# PROIECT_v30.net
KiCad netlist of a schematic drawn in EAGLE
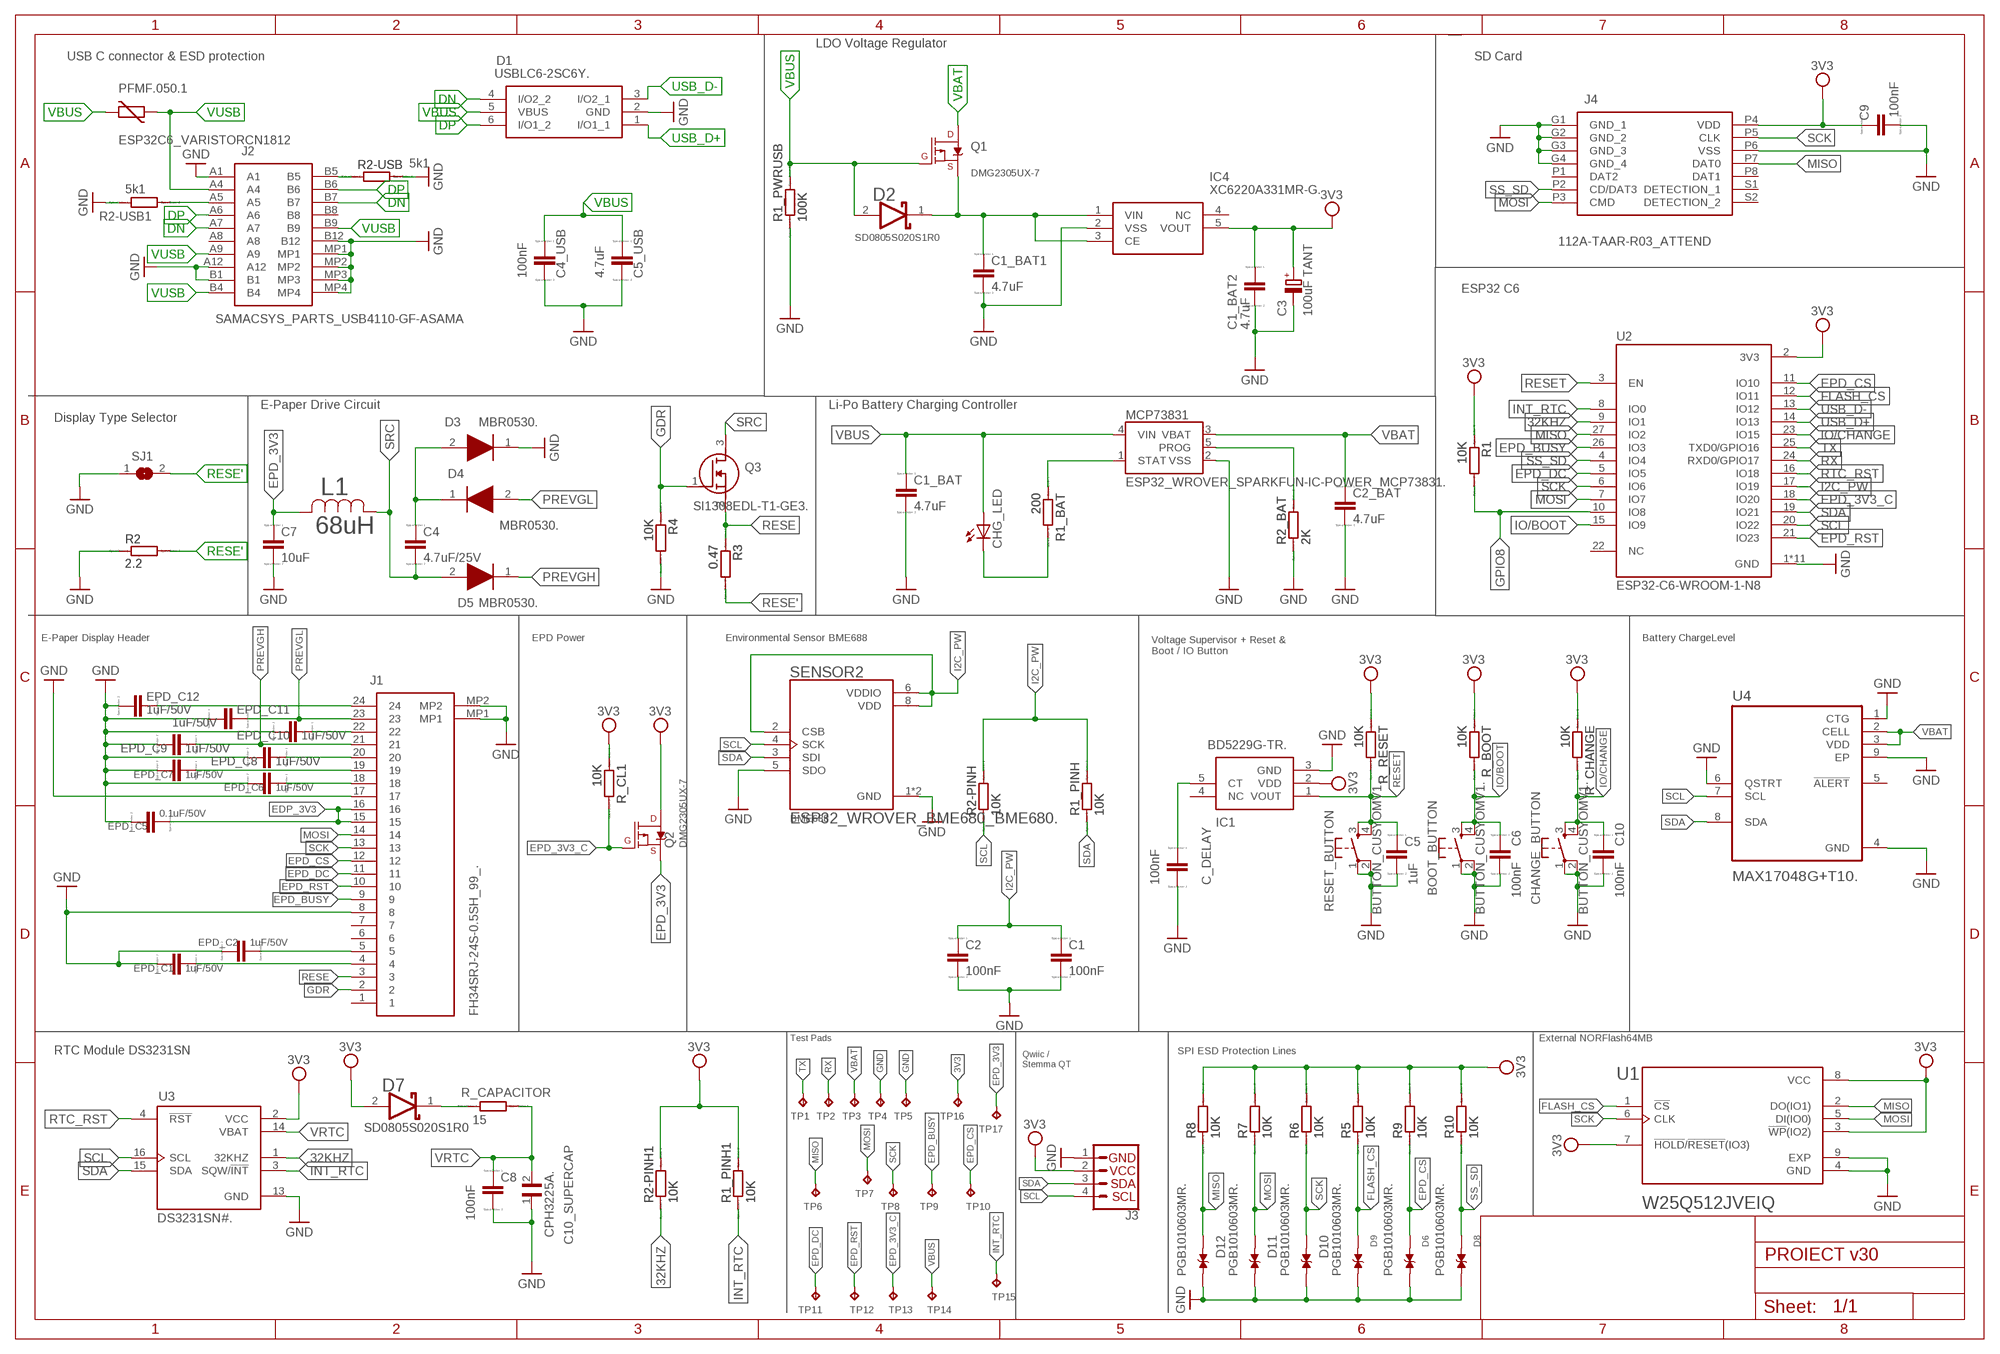
[diagram p0: schematic, sheet 1]

(export (version "E")
  (design (tool "Eeschema 10.0.6"))
  (components
    (comp (ref "BOOT_BUTTON")
      (value "BUTTON_CUSYOMV1.")
      (footprint "eagle-import:MYBUTTON")
      (libsource (lib "eagle-import") (part "BUTTON_CUSYOMV1."))
    )
    (comp (ref "C1")
      (value "100nF")
      (footprint "eagle-import:EAGLE-LTSPICE_C0402")
      (libsource (lib "eagle-import") (part "EAGLE-LTSPICE_CC0402"))
    )
    (comp (ref "C1_BAT")
      (value "4.7uF")
      (footprint "eagle-import:EAGLE-LTSPICE_C0402")
      (libsource (lib "eagle-import") (part "EAGLE-LTSPICE_CC0402"))
    )
    (comp (ref "C1_BAT1")
      (value "4.7uF")
      (footprint "eagle-import:EAGLE-LTSPICE_C0402")
      (libsource (lib "eagle-import") (part "EAGLE-LTSPICE_CC0402"))
    )
    (comp (ref "C1_BAT2")
      (value "4.7uF")
      (footprint "eagle-import:EAGLE-LTSPICE_C0402")
      (libsource (lib "eagle-import") (part "EAGLE-LTSPICE_CC0402"))
    )
    (comp (ref "C2")
      (value "100nF")
      (footprint "eagle-import:EAGLE-LTSPICE_C0402")
      (libsource (lib "eagle-import") (part "EAGLE-LTSPICE_CC0402"))
    )
    (comp (ref "C2_BAT")
      (value "4.7uF")
      (footprint "eagle-import:EAGLE-LTSPICE_C0402")
      (libsource (lib "eagle-import") (part "EAGLE-LTSPICE_CC0402"))
    )
    (comp (ref "C3")
      (value "100uF TANT")
      (footprint "eagle-import:RCL_CT3528")
      (libsource (lib "eagle-import") (part "RCL_CPOL-EUCT3528"))
    )
    (comp (ref "C4")
      (value "4.7uF/25V")
      (footprint "eagle-import:EAGLE-LTSPICE_C0402")
      (libsource (lib "eagle-import") (part "EAGLE-LTSPICE_CC0402"))
    )
    (comp (ref "C4_USB")
      (value "100nF")
      (footprint "eagle-import:EAGLE-LTSPICE_C0402")
      (libsource (lib "eagle-import") (part "EAGLE-LTSPICE_CC0402"))
    )
    (comp (ref "C5")
      (value "1uF")
      (footprint "eagle-import:EAGLE-LTSPICE_C0402")
      (libsource (lib "eagle-import") (part "EAGLE-LTSPICE_CC0402"))
    )
    (comp (ref "C5_USB")
      (value "4.7uF")
      (footprint "eagle-import:EAGLE-LTSPICE_C0402")
      (libsource (lib "eagle-import") (part "EAGLE-LTSPICE_CC0402"))
    )
    (comp (ref "C6")
      (value "100nF")
      (footprint "eagle-import:EAGLE-LTSPICE_C0402")
      (libsource (lib "eagle-import") (part "EAGLE-LTSPICE_CC0402"))
    )
    (comp (ref "C7")
      (value "10uF")
      (footprint "eagle-import:EAGLE-LTSPICE_C0402")
      (libsource (lib "eagle-import") (part "EAGLE-LTSPICE_CC0402"))
    )
    (comp (ref "C8")
      (value "100nF")
      (footprint "eagle-import:EAGLE-LTSPICE_C0402")
      (libsource (lib "eagle-import") (part "EAGLE-LTSPICE_CC0402"))
    )
    (comp (ref "C9")
      (value "100nF")
      (footprint "eagle-import:EAGLE-LTSPICE_C0402")
      (libsource (lib "eagle-import") (part "EAGLE-LTSPICE_CC0402"))
    )
    (comp (ref "C10")
      (value "100nF")
      (footprint "eagle-import:EAGLE-LTSPICE_C0402")
      (libsource (lib "eagle-import") (part "EAGLE-LTSPICE_CC0402"))
    )
    (comp (ref "C10_SUPERCAP")
      (value "CPH3225A.")
      (footprint "eagle-import:CAPCP3225X100N")
      (libsource (lib "eagle-import") (part "CPH3225A."))
    )
    (comp (ref "CHANGE_BUTTON")
      (value "BUTTON_CUSYOMV1.")
      (footprint "eagle-import:MYBUTTON")
      (libsource (lib "eagle-import") (part "BUTTON_CUSYOMV1."))
    )
    (comp (ref "CHG_LED")
      (value "ADAFRUIT_LEDCHIP-LED0603")
      (footprint "eagle-import:ADAFRUIT_CHIP-LED0603")
      (libsource (lib "eagle-import") (part "ADAFRUIT_LEDCHIP-LED0603"))
    )
    (comp (ref "C_DELAY")
      (value "100nF")
      (footprint "eagle-import:EAGLE-LTSPICE_C0402")
      (libsource (lib "eagle-import") (part "EAGLE-LTSPICE_CC0402"))
    )
    (comp (ref "D1")
      (value "USBLC6-2SC6Y.")
      (footprint "eagle-import:SOT95P280X145-6N")
      (libsource (lib "eagle-import") (part "USBLC6-2SC6Y."))
    )
    (comp (ref "D2")
      (value "ESP32_WROVER_AVX---SD0805S020S1R0_AVX_SD0805S020S1R0_0_0AVX_SD0805S020S1R0_0_0")
      (footprint "eagle-import:ESP32_WROVER_AVX---SD0805S020S1R0_AVX_SD0805S020S1R0_0")
      (fields (field (name "NUME") "SD0805S020S1R0"))
      (libsource (lib "eagle-import") (part "ESP32_WROVER_AVX---SD0805S020S1R0_AVX_SD0805S020S1R0_0_0AVX_SD0805S020S1R0_0_0"))
    )
    (comp (ref "D3")
      (value "MBR0530.")
      (footprint "eagle-import:SOD3716X135N")
      (libsource (lib "eagle-import") (part "MBR0530."))
    )
    (comp (ref "D4")
      (value "MBR0530.")
      (footprint "eagle-import:SOD3716X135N")
      (libsource (lib "eagle-import") (part "MBR0530."))
    )
    (comp (ref "D5")
      (value "MBR0530.")
      (footprint "eagle-import:SOD3716X135N")
      (libsource (lib "eagle-import") (part "MBR0530."))
    )
    (comp (ref "D6")
      (value "PGB1010603MR.")
      (footprint "eagle-import:DIOC1608X36N")
      (libsource (lib "eagle-import") (part "PGB1010603MR."))
    )
    (comp (ref "D7")
      (value "ESP32_WROVER_AVX---SD0805S020S1R0_AVX_SD0805S020S1R0_0_0AVX_SD0805S020S1R0_0_0")
      (footprint "eagle-import:ESP32_WROVER_AVX---SD0805S020S1R0_AVX_SD0805S020S1R0_0")
      (fields (field (name "NUME") "SD0805S020S1R0"))
      (libsource (lib "eagle-import") (part "ESP32_WROVER_AVX---SD0805S020S1R0_AVX_SD0805S020S1R0_0_0AVX_SD0805S020S1R0_0_0"))
    )
    (comp (ref "D8")
      (value "PGB1010603MR.")
      (footprint "eagle-import:DIOC1608X36N")
      (libsource (lib "eagle-import") (part "PGB1010603MR."))
    )
    (comp (ref "D9")
      (value "PGB1010603MR.")
      (footprint "eagle-import:DIOC1608X36N")
      (libsource (lib "eagle-import") (part "PGB1010603MR."))
    )
    (comp (ref "D10")
      (value "PGB1010603MR.")
      (footprint "eagle-import:DIOC1608X36N")
      (libsource (lib "eagle-import") (part "PGB1010603MR."))
    )
    (comp (ref "D11")
      (value "PGB1010603MR.")
      (footprint "eagle-import:DIOC1608X36N")
      (libsource (lib "eagle-import") (part "PGB1010603MR."))
    )
    (comp (ref "D12")
      (value "PGB1010603MR.")
      (footprint "eagle-import:DIOC1608X36N")
      (libsource (lib "eagle-import") (part "PGB1010603MR."))
    )
    (comp (ref "EPD_C1")
      (value "1uF/50V")
      (footprint "eagle-import:EAGLE-LTSPICE_C0402")
      (libsource (lib "eagle-import") (part "EAGLE-LTSPICE_CC0402"))
    )
    (comp (ref "EPD_C2")
      (value "1uF/50V")
      (footprint "eagle-import:EAGLE-LTSPICE_C0402")
      (libsource (lib "eagle-import") (part "EAGLE-LTSPICE_CC0402"))
    )
    (comp (ref "EPD_C5")
      (value "0.1uF/50V")
      (footprint "eagle-import:EAGLE-LTSPICE_C0402")
      (libsource (lib "eagle-import") (part "EAGLE-LTSPICE_CC0402"))
    )
    (comp (ref "EPD_C6")
      (value "1uF/50V")
      (footprint "eagle-import:EAGLE-LTSPICE_C0402")
      (libsource (lib "eagle-import") (part "EAGLE-LTSPICE_CC0402"))
    )
    (comp (ref "EPD_C7")
      (value "1uF/50V")
      (footprint "eagle-import:EAGLE-LTSPICE_C0402")
      (libsource (lib "eagle-import") (part "EAGLE-LTSPICE_CC0402"))
    )
    (comp (ref "EPD_C8")
      (value "1uF/50V")
      (footprint "eagle-import:EAGLE-LTSPICE_C0402")
      (libsource (lib "eagle-import") (part "EAGLE-LTSPICE_CC0402"))
    )
    (comp (ref "EPD_C9")
      (value "1uF/50V")
      (footprint "eagle-import:EAGLE-LTSPICE_C0402")
      (libsource (lib "eagle-import") (part "EAGLE-LTSPICE_CC0402"))
    )
    (comp (ref "EPD_C10")
      (value "1uF/50V")
      (footprint "eagle-import:EAGLE-LTSPICE_C0402")
      (libsource (lib "eagle-import") (part "EAGLE-LTSPICE_CC0402"))
    )
    (comp (ref "EPD_C11")
      (value "1uF/50V")
      (footprint "eagle-import:EAGLE-LTSPICE_C0402")
      (libsource (lib "eagle-import") (part "EAGLE-LTSPICE_CC0402"))
    )
    (comp (ref "EPD_C12")
      (value "1uF/50V")
      (footprint "eagle-import:EAGLE-LTSPICE_C0402")
      (libsource (lib "eagle-import") (part "EAGLE-LTSPICE_CC0402"))
    )
    (comp (ref "IC1")
      (value "BD5229G-TR.")
      (footprint "eagle-import:SOT95P280X125-5N")
      (libsource (lib "eagle-import") (part "BD5229G-TR."))
    )
    (comp (ref "IC4")
      (value "XC6220A331MR-G.")
      (footprint "eagle-import:SOT95P280X120-5N")
      (libsource (lib "eagle-import") (part "XC6220A331MR-G."))
    )
    (comp (ref "J1")
      (value "FH34SRJ-24S-0.5SH_99_.")
      (footprint "eagle-import:FH34SRJ24S05SH99")
      (libsource (lib "eagle-import") (part "FH34SRJ-24S-0.5SH_99_."))
    )
    (comp (ref "J2")
      (value "SAMACSYS_PARTS_USB4110-GF-ASAMA")
      (footprint "eagle-import:SAMACSYS_PARTS_USB4110GFA")
      (libsource (lib "eagle-import") (part "SAMACSYS_PARTS_USB4110-GF-ASAMA"))
    )
    (comp (ref "J3")
      (value "QWIIC_RIGHT_ANGLE")
      (footprint "eagle-import:JST04_1MM_RA")
      (libsource (lib "eagle-import") (part "QWIIC_CONNECTORJS-1MM"))
    )
    (comp (ref "J4")
      (value "112A-TAAR-R03_ATTEND")
      (footprint "eagle-import:112ATAARR03ATTEND")
      (fields (field (name "MANUFACTURER_PART_NUMBER") "112A-TAAR-R03 ATTEND"))
      (libsource (lib "eagle-import") (part "112A-TAAR-R03_ATTEND"))
    )
    (comp (ref "L1")
      (value "68uH")
      (footprint "eagle-import:IND_4828-WE-TPC_WRE")
      (libsource (lib "eagle-import") (part "744043680IND_4828-WE-TPC_WRE"))
    )
    (comp (ref "MCP73831")
      (value "ESP32_WROVER_SPARKFUN-IC-POWER_MCP73831.")
      (footprint "eagle-import:ESP32_WROVER_SPARKFUN-IC-POWER_SOT23-5")
      (libsource (lib "eagle-import") (part "ESP32_WROVER_SPARKFUN-IC-POWER_MCP73831."))
    )
    (comp (ref "PFMF.050.1")
      (value "ESP32C6_VARISTORCN1812")
      (footprint "eagle-import:ESP32C6_VARISTOR_CT_CN1812")
      (libsource (lib "eagle-import") (part "ESP32C6_VARISTORCN1812"))
    )
    (comp (ref "Q1")
      (value "20V/4.2A/52mΩ/1.4W")
      (footprint "eagle-import:ESP32_WROVER_SPARKFUN-DISCRETESEMI_SOT23-3")
      (fields (field (name "NUME") "DMG2305UX-7"))
      (libsource (lib "eagle-import") (part "ESP32_WROVER_SPARKFUN-DISCRETESEMI_MOSFET_PCH-DMG2305UX-7"))
    )
    (comp (ref "Q2")
      (value "20V/4.2A/52mΩ/1.4W")
      (footprint "eagle-import:ESP32_WROVER_SPARKFUN-DISCRETESEMI_SOT23-3")
      (fields (field (name "Q2") "DMG2305UX-7"))
      (libsource (lib "eagle-import") (part "ESP32_WROVER_SPARKFUN-DISCRETESEMI_MOSFET_PCH-DMG2305UX-7"))
    )
    (comp (ref "Q3")
      (value "SI1308EDL-T1-GE3.")
      (footprint "eagle-import:SOT65P210X110-3N")
      (libsource (lib "eagle-import") (part "SI1308EDL-T1-GE3."))
    )
    (comp (ref "R1")
      (value "10K")
      (footprint "eagle-import:ESP32_WROVER_EAGLE-LTSPICE_R0402")
      (libsource (lib "eagle-import") (part "ESP32_WROVER_EAGLE-LTSPICE_RR0402"))
    )
    (comp (ref "R1_BAT")
      (value "200")
      (footprint "eagle-import:ESP32_WROVER_EAGLE-LTSPICE_R0402")
      (libsource (lib "eagle-import") (part "ESP32_WROVER_EAGLE-LTSPICE_RR0402"))
    )
    (comp (ref "R1_PINH")
      (value "10K")
      (footprint "eagle-import:ESP32_WROVER_EAGLE-LTSPICE_R0402")
      (libsource (lib "eagle-import") (part "ESP32_WROVER_EAGLE-LTSPICE_RR0402"))
    )
    (comp (ref "R1_PINH1")
      (value "10K")
      (footprint "eagle-import:ESP32_WROVER_EAGLE-LTSPICE_R0402")
      (libsource (lib "eagle-import") (part "ESP32_WROVER_EAGLE-LTSPICE_RR0402"))
    )
    (comp (ref "R1_PWRUSB")
      (value "100K")
      (footprint "eagle-import:ESP32_WROVER_EAGLE-LTSPICE_R0402")
      (libsource (lib "eagle-import") (part "ESP32_WROVER_EAGLE-LTSPICE_RR0402"))
    )
    (comp (ref "R2")
      (value "2.2")
      (footprint "eagle-import:ESP32_WROVER_EAGLE-LTSPICE_R0402")
      (libsource (lib "eagle-import") (part "ESP32_WROVER_EAGLE-LTSPICE_RR0402"))
    )
    (comp (ref "R2-PINH")
      (value "10K")
      (footprint "eagle-import:ESP32_WROVER_EAGLE-LTSPICE_R0402")
      (libsource (lib "eagle-import") (part "ESP32_WROVER_EAGLE-LTSPICE_RR0402"))
    )
    (comp (ref "R2-PINH1")
      (value "10K")
      (footprint "eagle-import:ESP32_WROVER_EAGLE-LTSPICE_R0402")
      (libsource (lib "eagle-import") (part "ESP32_WROVER_EAGLE-LTSPICE_RR0402"))
    )
    (comp (ref "R2-USB")
      (value "5k1")
      (footprint "eagle-import:ESP32_WROVER_EAGLE-LTSPICE_R0402")
      (libsource (lib "eagle-import") (part "ESP32_WROVER_EAGLE-LTSPICE_RR0402"))
    )
    (comp (ref "R2-USB1")
      (value "5k1")
      (footprint "eagle-import:ESP32_WROVER_EAGLE-LTSPICE_R0402")
      (libsource (lib "eagle-import") (part "ESP32_WROVER_EAGLE-LTSPICE_RR0402"))
    )
    (comp (ref "R2_BAT")
      (value "2K")
      (footprint "eagle-import:ESP32_WROVER_EAGLE-LTSPICE_R0402")
      (libsource (lib "eagle-import") (part "ESP32_WROVER_EAGLE-LTSPICE_RR0402"))
    )
    (comp (ref "R3")
      (value "0.47")
      (footprint "eagle-import:ESP32_WROVER_EAGLE-LTSPICE_R0402")
      (libsource (lib "eagle-import") (part "ESP32_WROVER_EAGLE-LTSPICE_RR0402"))
    )
    (comp (ref "R4")
      (value "10K")
      (footprint "eagle-import:ESP32_WROVER_EAGLE-LTSPICE_R0402")
      (libsource (lib "eagle-import") (part "ESP32_WROVER_EAGLE-LTSPICE_RR0402"))
    )
    (comp (ref "R5")
      (value "10K")
      (footprint "eagle-import:ESP32_WROVER_EAGLE-LTSPICE_R0402")
      (libsource (lib "eagle-import") (part "ESP32_WROVER_EAGLE-LTSPICE_RR0402"))
    )
    (comp (ref "R6")
      (value "10K")
      (footprint "eagle-import:ESP32_WROVER_EAGLE-LTSPICE_R0402")
      (libsource (lib "eagle-import") (part "ESP32_WROVER_EAGLE-LTSPICE_RR0402"))
    )
    (comp (ref "R7")
      (value "10K")
      (footprint "eagle-import:ESP32_WROVER_EAGLE-LTSPICE_R0402")
      (libsource (lib "eagle-import") (part "ESP32_WROVER_EAGLE-LTSPICE_RR0402"))
    )
    (comp (ref "R8")
      (value "10K")
      (footprint "eagle-import:ESP32_WROVER_EAGLE-LTSPICE_R0402")
      (libsource (lib "eagle-import") (part "ESP32_WROVER_EAGLE-LTSPICE_RR0402"))
    )
    (comp (ref "R9")
      (value "10K")
      (footprint "eagle-import:ESP32_WROVER_EAGLE-LTSPICE_R0402")
      (libsource (lib "eagle-import") (part "ESP32_WROVER_EAGLE-LTSPICE_RR0402"))
    )
    (comp (ref "R10")
      (value "10K")
      (footprint "eagle-import:ESP32_WROVER_EAGLE-LTSPICE_R0402")
      (libsource (lib "eagle-import") (part "ESP32_WROVER_EAGLE-LTSPICE_RR0402"))
    )
    (comp (ref "RESET_BUTTON")
      (value "BUTTON_CUSYOMV1.")
      (footprint "eagle-import:MYBUTTON")
      (libsource (lib "eagle-import") (part "BUTTON_CUSYOMV1."))
    )
    (comp (ref "R_BOOT")
      (value "10K")
      (footprint "eagle-import:ESP32_WROVER_EAGLE-LTSPICE_R0402")
      (libsource (lib "eagle-import") (part "ESP32_WROVER_EAGLE-LTSPICE_RR0402"))
    )
    (comp (ref "R_CAPACITOR")
      (value "15")
      (footprint "eagle-import:ESP32_WROVER_EAGLE-LTSPICE_R0402")
      (libsource (lib "eagle-import") (part "ESP32_WROVER_EAGLE-LTSPICE_RR0402"))
    )
    (comp (ref "R_CHANGE")
      (value "10K")
      (footprint "eagle-import:ESP32_WROVER_EAGLE-LTSPICE_R0402")
      (libsource (lib "eagle-import") (part "ESP32_WROVER_EAGLE-LTSPICE_RR0402"))
    )
    (comp (ref "R_CL1")
      (value "10K")
      (footprint "eagle-import:ESP32_WROVER_EAGLE-LTSPICE_R0402")
      (libsource (lib "eagle-import") (part "ESP32_WROVER_EAGLE-LTSPICE_RR0402"))
    )
    (comp (ref "R_RESET")
      (value "10K")
      (footprint "eagle-import:ESP32_WROVER_EAGLE-LTSPICE_R0402")
      (libsource (lib "eagle-import") (part "ESP32_WROVER_EAGLE-LTSPICE_RR0402"))
    )
    (comp (ref "SENSOR2")
      (value "ESP32_WROVER_BME680_BME680.")
      (footprint "eagle-import:ESP32_WROVER_BME680_PSON80P300X300X100-8N")
      (fields (field (name "NUME") "BME688"))
      (libsource (lib "eagle-import") (part "ESP32_WROVER_BME680_BME680."))
    )
    (comp (ref "SJ1")
      (value "SJ.")
      (footprint "eagle-import:SJ")
      (libsource (lib "eagle-import") (part "SJ."))
    )
    (comp (ref "TP1")
      (value "TPTP20R")
      (footprint "eagle-import:TP20R")
      (libsource (lib "eagle-import") (part "TPTP20R"))
    )
    (comp (ref "TP2")
      (value "TPTP20R")
      (footprint "eagle-import:TP20R")
      (libsource (lib "eagle-import") (part "TPTP20R"))
    )
    (comp (ref "TP3")
      (value "TPTP20R")
      (footprint "eagle-import:TP20R")
      (libsource (lib "eagle-import") (part "TPTP20R"))
    )
    (comp (ref "TP4")
      (value "TPTP20R")
      (footprint "eagle-import:TP20R")
      (libsource (lib "eagle-import") (part "TPTP20R"))
    )
    (comp (ref "TP5")
      (value "TPTP20R")
      (footprint "eagle-import:TP20R")
      (libsource (lib "eagle-import") (part "TPTP20R"))
    )
    (comp (ref "TP6")
      (value "TPTP20R")
      (footprint "eagle-import:TP20R")
      (libsource (lib "eagle-import") (part "TPTP20R"))
    )
    (comp (ref "TP7")
      (value "TPTP20R")
      (footprint "eagle-import:TP20R")
      (libsource (lib "eagle-import") (part "TPTP20R"))
    )
    (comp (ref "TP8")
      (value "TPTP20R")
      (footprint "eagle-import:TP20R")
      (libsource (lib "eagle-import") (part "TPTP20R"))
    )
    (comp (ref "TP9")
      (value "TPTP20R")
      (footprint "eagle-import:TP20R")
      (libsource (lib "eagle-import") (part "TPTP20R"))
    )
    (comp (ref "TP10")
      (value "TPTP20R")
      (footprint "eagle-import:TP20R")
      (libsource (lib "eagle-import") (part "TPTP20R"))
    )
    (comp (ref "TP11")
      (value "TPTP20R")
      (footprint "eagle-import:TP20R")
      (libsource (lib "eagle-import") (part "TPTP20R"))
    )
    (comp (ref "TP12")
      (value "TPTP20R")
      (footprint "eagle-import:TP20R")
      (libsource (lib "eagle-import") (part "TPTP20R"))
    )
    (comp (ref "TP13")
      (value "TPTP20R")
      (footprint "eagle-import:TP20R")
      (libsource (lib "eagle-import") (part "TPTP20R"))
    )
    (comp (ref "TP14")
      (value "TPTP20R")
      (footprint "eagle-import:TP20R")
      (libsource (lib "eagle-import") (part "TPTP20R"))
    )
    (comp (ref "TP15")
      (value "TPTP20R")
      (footprint "eagle-import:TP20R")
      (libsource (lib "eagle-import") (part "TPTP20R"))
    )
    (comp (ref "TP16")
      (value "TPTP20R")
      (footprint "eagle-import:TP20R")
      (libsource (lib "eagle-import") (part "TPTP20R"))
    )
    (comp (ref "TP17")
      (value "TPTP20R")
      (footprint "eagle-import:TP20R")
      (libsource (lib "eagle-import") (part "TPTP20R"))
    )
    (comp (ref "U1")
      (value "W25Q512JVEIQ")
      (footprint "eagle-import:SON127P600X800X80-9N")
      (fields (field (name "MF") "Winbond Electronics"))
      (libsource (lib "eagle-import") (part "W25Q512JVEIQ"))
    )
    (comp (ref "U2")
      (value "ESP32-C6-WROOM-1-N8")
      (footprint "eagle-import:XCVR_ESP32-C6-WROOM-1-N8")
      (fields (field (name "MF") "Espressif Systems"))
      (libsource (lib "eagle-import") (part "ESP32-C6-WROOM-1-N8"))
    )
    (comp (ref "U3")
      (value "DS3231SN#.")
      (footprint "eagle-import:SOIC127P1032X265-16N")
      (libsource (lib "eagle-import") (part "DS3231SN#."))
    )
    (comp (ref "U4")
      (value "MAX17048G+T10.")
      (footprint "eagle-import:SON50P200X200X80-9N")
      (libsource (lib "eagle-import") (part "MAX17048G+T10."))
    )
  )
  (nets
    (net (code "1") (name "3V3") (class "Default")
      (node (ref "C1_BAT2") (pin "1") (pinfunction "1_1") (pintype "passive"))
      (node (ref "C3") (pin "+") (pinfunction "+_+") (pintype "passive"))
      (node (ref "C9") (pin "1") (pinfunction "1_1") (pintype "passive"))
      (node (ref "D7") (pin "2") (pinfunction "ANODE_2") (pintype "bidirectional"))
      (node (ref "IC1") (pin "2") (pinfunction "VDD_2") (pintype "bidirectional"))
      (node (ref "IC4") (pin "5") (pinfunction "VOUT_5") (pintype "bidirectional"))
      (node (ref "J3") (pin "2") (pinfunction "2_2") (pintype "power_in"))
      (node (ref "J4") (pin "P4") (pinfunction "VDD_P4") (pintype "bidirectional"))
      (node (ref "Q2") (pin "3") (pinfunction "D_3") (pintype "bidirectional"))
      (node (ref "R1") (pin "1") (pinfunction "1_1") (pintype "passive"))
      (node (ref "R10") (pin "2") (pinfunction "2_2") (pintype "passive"))
      (node (ref "R1_PINH1") (pin "2") (pinfunction "2_2") (pintype "passive"))
      (node (ref "R2-PINH1") (pin "2") (pinfunction "2_2") (pintype "passive"))
      (node (ref "R5") (pin "2") (pinfunction "2_2") (pintype "passive"))
      (node (ref "R6") (pin "2") (pinfunction "2_2") (pintype "passive"))
      (node (ref "R7") (pin "2") (pinfunction "2_2") (pintype "passive"))
      (node (ref "R8") (pin "2") (pinfunction "2_2") (pintype "passive"))
      (node (ref "R9") (pin "2") (pinfunction "2_2") (pintype "passive"))
      (node (ref "R_BOOT") (pin "1") (pinfunction "1_1") (pintype "passive"))
      (node (ref "R_CHANGE") (pin "1") (pinfunction "1_1") (pintype "passive"))
      (node (ref "R_CL1") (pin "1") (pinfunction "1_1") (pintype "passive"))
      (node (ref "R_RESET") (pin "1") (pinfunction "1_1") (pintype "passive"))
      (node (ref "TP16") (pin "TP") (pinfunction "TP_TP") (pintype "input"))
      (node (ref "U1") (pin "3") (pinfunction "~{WP}(IO2)_3") (pintype "bidirectional"))
      (node (ref "U1") (pin "7") (pinfunction "~{HOLD}/~{RESET}(IO3)_7") (pintype "bidirectional"))
      (node (ref "U1") (pin "8") (pinfunction "VCC_8") (pintype "power_in"))
      (node (ref "U2") (pin "2") (pinfunction "3V3_2") (pintype "power_in"))
      (node (ref "U3") (pin "2") (pinfunction "VCC_2") (pintype "power_in"))
    )
    (net (code "2") (name "32KHZ") (class "Default")
      (node (ref "R2-PINH1") (pin "1") (pinfunction "1_1") (pintype "passive"))
      (node (ref "U2") (pin "9") (pinfunction "IO1_9") (pintype "bidirectional"))
      (node (ref "U3") (pin "1") (pinfunction "32KHZ_1") (pintype "output"))
    )
    (net (code "3") (name "DN") (class "Default")
      (node (ref "D1") (pin "4") (pinfunction "I/O2_2_4") (pintype "bidirectional"))
      (node (ref "J2") (pin "A7") (pinfunction "A7_A7") (pintype "bidirectional"))
      (node (ref "J2") (pin "B7") (pinfunction "B7_B7") (pintype "bidirectional"))
    )
    (net (code "4") (name "DP") (class "Default")
      (node (ref "D1") (pin "6") (pinfunction "I/O1_2_6") (pintype "bidirectional"))
      (node (ref "J2") (pin "A6") (pinfunction "A6_A6") (pintype "bidirectional"))
      (node (ref "J2") (pin "B6") (pinfunction "B6_B6") (pintype "bidirectional"))
    )
    (net (code "5") (name "EDP_3V3") (class "Default")
      (node (ref "EPD_C5") (pin "1") (pinfunction "1_1") (pintype "passive"))
      (node (ref "J1") (pin "15") (pinfunction "15_15") (pintype "bidirectional"))
      (node (ref "J1") (pin "16") (pinfunction "16_16") (pintype "bidirectional"))
    )
    (net (code "6") (name "EPD_3V3") (class "Default")
      (node (ref "C7") (pin "1") (pinfunction "1_1") (pintype "passive"))
      (node (ref "L1") (pin "2") (pinfunction "2_2") (pintype "passive"))
      (node (ref "Q2") (pin "2") (pinfunction "S_2") (pintype "bidirectional"))
      (node (ref "TP17") (pin "TP") (pinfunction "TP_TP") (pintype "input"))
    )
    (net (code "7") (name "EPD_3V3_C") (class "Default")
      (node (ref "Q2") (pin "1") (pinfunction "G_1") (pintype "bidirectional"))
      (node (ref "R_CL1") (pin "2") (pinfunction "2_2") (pintype "passive"))
      (node (ref "TP13") (pin "TP") (pinfunction "TP_TP") (pintype "input"))
      (node (ref "U2") (pin "18") (pinfunction "IO20_18") (pintype "bidirectional"))
    )
    (net (code "8") (name "EPD_BUSY") (class "Default")
      (node (ref "J1") (pin "9") (pinfunction "9_9") (pintype "bidirectional"))
      (node (ref "TP9") (pin "TP") (pinfunction "TP_TP") (pintype "input"))
      (node (ref "U2") (pin "26") (pinfunction "IO3_26") (pintype "bidirectional"))
    )
    (net (code "9") (name "EPD_CS") (class "Default")
      (node (ref "D6") (pin "1") (pinfunction "1_1") (pintype "passive"))
      (node (ref "J1") (pin "12") (pinfunction "12_12") (pintype "bidirectional"))
      (node (ref "R9") (pin "1") (pinfunction "1_1") (pintype "passive"))
      (node (ref "TP10") (pin "TP") (pinfunction "TP_TP") (pintype "input"))
      (node (ref "U2") (pin "11") (pinfunction "IO10_11") (pintype "bidirectional"))
    )
    (net (code "10") (name "EPD_DC") (class "Default")
      (node (ref "J1") (pin "11") (pinfunction "11_11") (pintype "bidirectional"))
      (node (ref "TP11") (pin "TP") (pinfunction "TP_TP") (pintype "input"))
      (node (ref "U2") (pin "5") (pinfunction "IO5_5") (pintype "bidirectional"))
    )
    (net (code "11") (name "EPD_RST") (class "Default")
      (node (ref "J1") (pin "10") (pinfunction "10_10") (pintype "bidirectional"))
      (node (ref "TP12") (pin "TP") (pinfunction "TP_TP") (pintype "input"))
      (node (ref "U2") (pin "21") (pinfunction "IO23_21") (pintype "bidirectional"))
    )
    (net (code "12") (name "FLASH_CS") (class "Default")
      (node (ref "D9") (pin "1") (pinfunction "1_1") (pintype "passive"))
      (node (ref "R5") (pin "1") (pinfunction "1_1") (pintype "passive"))
      (node (ref "U1") (pin "1") (pinfunction "~{CS}_1") (pintype "input"))
      (node (ref "U2") (pin "12") (pinfunction "IO11_12") (pintype "bidirectional"))
    )
    (net (code "13") (name "GDR") (class "Default")
      (node (ref "J1") (pin "2") (pinfunction "2_2") (pintype "bidirectional"))
      (node (ref "Q3") (pin "1") (pinfunction "G_1") (pintype "bidirectional"))
      (node (ref "R4") (pin "1") (pinfunction "1_1") (pintype "passive"))
    )
    (net (code "14") (name "GND") (class "Default")
      (node (ref "BOOT_BUTTON") (pin "1") (pinfunction "1_1") (pintype "passive"))
      (node (ref "BOOT_BUTTON") (pin "2") (pinfunction "2_2") (pintype "passive"))
      (node (ref "C1") (pin "2") (pinfunction "2_2") (pintype "passive"))
      (node (ref "C10") (pin "2") (pinfunction "2_2") (pintype "passive"))
      (node (ref "C10_SUPERCAP") (pin "1") (pinfunction "1_1") (pintype "passive"))
      (node (ref "C1_BAT") (pin "2") (pinfunction "2_2") (pintype "passive"))
      (node (ref "C1_BAT1") (pin "2") (pinfunction "2_2") (pintype "passive"))
      (node (ref "C1_BAT2") (pin "2") (pinfunction "2_2") (pintype "passive"))
      (node (ref "C2") (pin "2") (pinfunction "2_2") (pintype "passive"))
      (node (ref "C2_BAT") (pin "2") (pinfunction "2_2") (pintype "passive"))
      (node (ref "C3") (pin "-") (pinfunction "-_-") (pintype "passive"))
      (node (ref "C4_USB") (pin "2") (pinfunction "2_2") (pintype "passive"))
      (node (ref "C5") (pin "2") (pinfunction "2_2") (pintype "passive"))
      (node (ref "C5_USB") (pin "2") (pinfunction "2_2") (pintype "passive"))
      (node (ref "C6") (pin "2") (pinfunction "2_2") (pintype "passive"))
      (node (ref "C7") (pin "2") (pinfunction "2_2") (pintype "passive"))
      (node (ref "C8") (pin "2") (pinfunction "2_2") (pintype "passive"))
      (node (ref "C9") (pin "2") (pinfunction "2_2") (pintype "passive"))
      (node (ref "CHANGE_BUTTON") (pin "1") (pinfunction "1_1") (pintype "passive"))
      (node (ref "CHANGE_BUTTON") (pin "2") (pinfunction "2_2") (pintype "passive"))
      (node (ref "C_DELAY") (pin "2") (pinfunction "2_2") (pintype "passive"))
      (node (ref "D1") (pin "2") (pinfunction "GND_2") (pintype "bidirectional"))
      (node (ref "D10") (pin "2") (pinfunction "2_2") (pintype "passive"))
      (node (ref "D11") (pin "2") (pinfunction "2_2") (pintype "passive"))
      (node (ref "D12") (pin "2") (pinfunction "2_2") (pintype "passive"))
      (node (ref "D3") (pin "1") (pinfunction "K_1") (pintype "bidirectional"))
      (node (ref "D6") (pin "2") (pinfunction "2_2") (pintype "passive"))
      (node (ref "D8") (pin "2") (pinfunction "2_2") (pintype "passive"))
      (node (ref "D9") (pin "2") (pinfunction "2_2") (pintype "passive"))
      (node (ref "EPD_C1") (pin "2") (pinfunction "2_2") (pintype "passive"))
      (node (ref "EPD_C10") (pin "2") (pinfunction "2_2") (pintype "passive"))
      (node (ref "EPD_C11") (pin "2") (pinfunction "2_2") (pintype "passive"))
      (node (ref "EPD_C12") (pin "2") (pinfunction "2_2") (pintype "passive"))
      (node (ref "EPD_C2") (pin "2") (pinfunction "2_2") (pintype "passive"))
      (node (ref "EPD_C5") (pin "2") (pinfunction "2_2") (pintype "passive"))
      (node (ref "EPD_C6") (pin "2") (pinfunction "2_2") (pintype "passive"))
      (node (ref "EPD_C7") (pin "2") (pinfunction "2_2") (pintype "passive"))
      (node (ref "EPD_C8") (pin "2") (pinfunction "2_2") (pintype "passive"))
      (node (ref "EPD_C9") (pin "2") (pinfunction "2_2") (pintype "passive"))
      (node (ref "IC1") (pin "3") (pinfunction "GND_3") (pintype "bidirectional"))
      (node (ref "IC4") (pin "2") (pinfunction "VSS_2") (pintype "bidirectional"))
      (node (ref "J1") (pin "17") (pinfunction "17_17") (pintype "bidirectional"))
      (node (ref "J1") (pin "8") (pinfunction "8_8") (pintype "bidirectional"))
      (node (ref "J1") (pin "MP1") (pinfunction "MP1_MP1") (pintype "bidirectional"))
      (node (ref "J1") (pin "MP2") (pinfunction "MP2_MP2") (pintype "bidirectional"))
      (node (ref "J2") (pin "A1") (pinfunction "A1_A1") (pintype "bidirectional"))
      (node (ref "J2") (pin "A12") (pinfunction "A12_A12") (pintype "bidirectional"))
      (node (ref "J2") (pin "B1") (pinfunction "B1_B1") (pintype "bidirectional"))
      (node (ref "J2") (pin "B12") (pinfunction "B12_B12") (pintype "bidirectional"))
      (node (ref "J2") (pin "MP1") (pinfunction "MP1_MP1") (pintype "bidirectional"))
      (node (ref "J2") (pin "MP2") (pinfunction "MP2_MP2") (pintype "bidirectional"))
      (node (ref "J2") (pin "MP3") (pinfunction "MP3_MP3") (pintype "bidirectional"))
      (node (ref "J2") (pin "MP4") (pinfunction "MP4_MP4") (pintype "bidirectional"))
      (node (ref "J3") (pin "1") (pinfunction "1_1") (pintype "power_in"))
      (node (ref "J4") (pin "G1") (pinfunction "GND_1_G1") (pintype "bidirectional"))
      (node (ref "J4") (pin "G2") (pinfunction "GND_2_G2") (pintype "bidirectional"))
      (node (ref "J4") (pin "G3") (pinfunction "GND_3_G3") (pintype "bidirectional"))
      (node (ref "J4") (pin "G4") (pinfunction "GND_4_G4") (pintype "bidirectional"))
      (node (ref "J4") (pin "P6") (pinfunction "VSS_P6") (pintype "bidirectional"))
      (node (ref "MCP73831") (pin "2") (pinfunction "VSS_2") (pintype "power_in"))
      (node (ref "R1_PWRUSB") (pin "1") (pinfunction "1_1") (pintype "passive"))
      (node (ref "R2") (pin "1") (pinfunction "1_1") (pintype "passive"))
      (node (ref "R2-USB") (pin "2") (pinfunction "2_2") (pintype "passive"))
      (node (ref "R2-USB1") (pin "1") (pinfunction "1_1") (pintype "passive"))
      (node (ref "R2_BAT") (pin "1") (pinfunction "1_1") (pintype "passive"))
      (node (ref "R4") (pin "2") (pinfunction "2_2") (pintype "passive"))
      (node (ref "RESET_BUTTON") (pin "1") (pinfunction "1_1") (pintype "passive"))
      (node (ref "RESET_BUTTON") (pin "2") (pinfunction "2_2") (pintype "passive"))
      (node (ref "SENSOR2") (pin "1") (pinfunction "GND_1") (pintype "power_in"))
      (node (ref "SENSOR2") (pin "5") (pinfunction "SDO_5") (pintype "bidirectional"))
      (node (ref "SENSOR2") (pin "7") (pinfunction "GND_7") (pintype "power_in"))
      (node (ref "SJ1") (pin "1") (pinfunction "1_1") (pintype "passive"))
      (node (ref "TP4") (pin "TP") (pinfunction "TP_TP") (pintype "input"))
      (node (ref "TP5") (pin "TP") (pinfunction "TP_TP") (pintype "input"))
      (node (ref "U1") (pin "4") (pinfunction "GND_4") (pintype "power_in"))
      (node (ref "U1") (pin "9") (pinfunction "EXP_9") (pintype "passive"))
      (node (ref "U2") (pin "1") (pinfunction "GND_1") (pintype "power_in"))
      (node (ref "U2") (pin "28") (pinfunction "GND_28") (pintype "power_in"))
      (node (ref "U2") (pin "29_1") (pinfunction "GND_29_1") (pintype "power_in"))
      (node (ref "U2") (pin "29_2") (pinfunction "GND_29_2") (pintype "power_in"))
      (node (ref "U2") (pin "29_3") (pinfunction "GND_29_3") (pintype "power_in"))
      (node (ref "U2") (pin "29_4") (pinfunction "GND_29_4") (pintype "power_in"))
      (node (ref "U2") (pin "29_5") (pinfunction "GND_29_5") (pintype "power_in"))
      (node (ref "U2") (pin "29_6") (pinfunction "GND_29_6") (pintype "power_in"))
      (node (ref "U2") (pin "29_7") (pinfunction "GND_29_7") (pintype "power_in"))
      (node (ref "U2") (pin "29_8") (pinfunction "GND_29_8") (pintype "power_in"))
      (node (ref "U2") (pin "29_9") (pinfunction "GND_29_9") (pintype "power_in"))
      (node (ref "U3") (pin "13") (pinfunction "GND_13") (pintype "power_in"))
      (node (ref "U4") (pin "1") (pinfunction "CTG_1") (pintype "power_in"))
      (node (ref "U4") (pin "4") (pinfunction "GND_4") (pintype "power_in"))
      (node (ref "U4") (pin "6") (pinfunction "QSTRT_6") (pintype "input"))
      (node (ref "U4") (pin "9") (pinfunction "EP_9") (pintype "power_in"))
    )
    (net (code "15") (name "GPIO8") (class "Default")
      (node (ref "R1") (pin "2") (pinfunction "2_2") (pintype "passive"))
      (node (ref "U2") (pin "10") (pinfunction "IO8_10") (pintype "bidirectional"))
    )
    (net (code "16") (name "I2C_PW") (class "Default")
      (node (ref "C1") (pin "1") (pinfunction "1_1") (pintype "passive"))
      (node (ref "C2") (pin "1") (pinfunction "1_1") (pintype "passive"))
      (node (ref "R1_PINH") (pin "2") (pinfunction "2_2") (pintype "passive"))
      (node (ref "R2-PINH") (pin "2") (pinfunction "2_2") (pintype "passive"))
      (node (ref "SENSOR2") (pin "2") (pinfunction "CSB_2") (pintype "input"))
      (node (ref "SENSOR2") (pin "6") (pinfunction "VDDIO_6") (pintype "power_in"))
      (node (ref "SENSOR2") (pin "8") (pinfunction "VDD_8") (pintype "power_in"))
      (node (ref "U2") (pin "17") (pinfunction "IO19_17") (pintype "bidirectional"))
    )
    (net (code "17") (name "INT_RTC") (class "Default")
      (node (ref "R1_PINH1") (pin "1") (pinfunction "1_1") (pintype "passive"))
      (node (ref "TP15") (pin "TP") (pinfunction "TP_TP") (pintype "input"))
      (node (ref "U2") (pin "8") (pinfunction "IO0_8") (pintype "bidirectional"))
      (node (ref "U3") (pin "3") (pinfunction "SQW/~{INT}_3") (pintype "output"))
    )
    (net (code "18") (name "IO{slash}BOOT") (class "Default")
      (node (ref "BOOT_BUTTON") (pin "3") (pinfunction "3_3") (pintype "passive"))
      (node (ref "BOOT_BUTTON") (pin "4") (pinfunction "4_4") (pintype "passive"))
      (node (ref "C6") (pin "1") (pinfunction "1_1") (pintype "passive"))
      (node (ref "R_BOOT") (pin "2") (pinfunction "2_2") (pintype "passive"))
      (node (ref "U2") (pin "15") (pinfunction "IO9_15") (pintype "bidirectional"))
    )
    (net (code "19") (name "IO{slash}CHANGE") (class "Default")
      (node (ref "C10") (pin "1") (pinfunction "1_1") (pintype "passive"))
      (node (ref "CHANGE_BUTTON") (pin "3") (pinfunction "3_3") (pintype "passive"))
      (node (ref "CHANGE_BUTTON") (pin "4") (pinfunction "4_4") (pintype "passive"))
      (node (ref "R_CHANGE") (pin "2") (pinfunction "2_2") (pintype "passive"))
      (node (ref "U2") (pin "23") (pinfunction "IO15_23") (pintype "bidirectional"))
    )
    (net (code "20") (name "MISO") (class "Default")
      (node (ref "D12") (pin "1") (pinfunction "1_1") (pintype "passive"))
      (node (ref "J4") (pin "P7") (pinfunction "DAT0_P7") (pintype "bidirectional"))
      (node (ref "R8") (pin "1") (pinfunction "1_1") (pintype "passive"))
      (node (ref "TP6") (pin "TP") (pinfunction "TP_TP") (pintype "input"))
      (node (ref "U1") (pin "2") (pinfunction "DO(IO1)_2") (pintype "bidirectional"))
      (node (ref "U2") (pin "27") (pinfunction "IO2_27") (pintype "bidirectional"))
    )
    (net (code "21") (name "MOSI") (class "Default")
      (node (ref "D11") (pin "1") (pinfunction "1_1") (pintype "passive"))
      (node (ref "J1") (pin "14") (pinfunction "14_14") (pintype "bidirectional"))
      (node (ref "J4") (pin "P3") (pinfunction "CMD_P3") (pintype "bidirectional"))
      (node (ref "R7") (pin "1") (pinfunction "1_1") (pintype "passive"))
      (node (ref "TP7") (pin "TP") (pinfunction "TP_TP") (pintype "input"))
      (node (ref "U1") (pin "5") (pinfunction "DI(IO0)_5") (pintype "bidirectional"))
      (node (ref "U2") (pin "7") (pinfunction "IO7_7") (pintype "bidirectional"))
    )
    (net (code "22") (name "Net-(CHG_LED-PadC)") (class "Default")
      (node (ref "CHG_LED") (pin "C") (pinfunction "C_C") (pintype "passive"))
      (node (ref "R1_BAT") (pin "2") (pinfunction "2_2") (pintype "passive"))
    )
    (net (code "23") (name "Net-(D2-CATHODE)") (class "Default")
      (node (ref "C1_BAT1") (pin "1") (pinfunction "1_1") (pintype "passive"))
      (node (ref "D2") (pin "1") (pinfunction "CATHODE_1") (pintype "bidirectional"))
      (node (ref "IC4") (pin "1") (pinfunction "VIN_1") (pintype "bidirectional"))
      (node (ref "IC4") (pin "3") (pinfunction "CE_3") (pintype "bidirectional"))
      (node (ref "Q1") (pin "2") (pinfunction "S_2") (pintype "bidirectional"))
    )
    (net (code "24") (name "Net-(D3-A)") (class "Default")
      (node (ref "C4") (pin "1") (pinfunction "1_1") (pintype "passive"))
      (node (ref "D3") (pin "2") (pinfunction "A_2") (pintype "bidirectional"))
      (node (ref "D4") (pin "1") (pinfunction "K_1") (pintype "bidirectional"))
    )
    (net (code "25") (name "Net-(D7-CATHODE)") (class "Default")
      (node (ref "D7") (pin "1") (pinfunction "CATHODE_1") (pintype "bidirectional"))
      (node (ref "R_CAPACITOR") (pin "2") (pinfunction "2_2") (pintype "passive"))
    )
    (net (code "26") (name "Net-(EPD_C1-Pad1)") (class "Default")
      (node (ref "EPD_C1") (pin "1") (pinfunction "1_1") (pintype "passive"))
      (node (ref "J1") (pin "4") (pinfunction "4_4") (pintype "bidirectional"))
    )
    (net (code "27") (name "Net-(EPD_C2-Pad1)") (class "Default")
      (node (ref "EPD_C2") (pin "1") (pinfunction "1_1") (pintype "passive"))
      (node (ref "J1") (pin "5") (pinfunction "5_5") (pintype "bidirectional"))
    )
    (net (code "28") (name "Net-(EPD_C6-Pad1)") (class "Default")
      (node (ref "EPD_C6") (pin "1") (pinfunction "1_1") (pintype "passive"))
      (node (ref "J1") (pin "18") (pinfunction "18_18") (pintype "bidirectional"))
    )
    (net (code "29") (name "Net-(EPD_C7-Pad1)") (class "Default")
      (node (ref "EPD_C7") (pin "1") (pinfunction "1_1") (pintype "passive"))
      (node (ref "J1") (pin "19") (pinfunction "19_19") (pintype "bidirectional"))
    )
    (net (code "30") (name "Net-(EPD_C8-Pad1)") (class "Default")
      (node (ref "EPD_C8") (pin "1") (pinfunction "1_1") (pintype "passive"))
      (node (ref "J1") (pin "20") (pinfunction "20_20") (pintype "bidirectional"))
    )
    (net (code "31") (name "Net-(EPD_C10-Pad1)") (class "Default")
      (node (ref "EPD_C10") (pin "1") (pinfunction "1_1") (pintype "passive"))
      (node (ref "J1") (pin "22") (pinfunction "22_22") (pintype "bidirectional"))
    )
    (net (code "32") (name "Net-(EPD_C12-Pad1)") (class "Default")
      (node (ref "EPD_C12") (pin "1") (pinfunction "1_1") (pintype "passive"))
      (node (ref "J1") (pin "24") (pinfunction "24_24") (pintype "bidirectional"))
    )
    (net (code "33") (name "Net-(IC1-CT)") (class "Default")
      (node (ref "C_DELAY") (pin "1") (pinfunction "1_1") (pintype "passive"))
      (node (ref "IC1") (pin "5") (pinfunction "CT_5") (pintype "bidirectional"))
    )
    (net (code "34") (name "Net-(J2-PadA5)") (class "Default")
      (node (ref "J2") (pin "A5") (pinfunction "A5_A5") (pintype "bidirectional"))
      (node (ref "R2-USB1") (pin "2") (pinfunction "2_2") (pintype "passive"))
    )
    (net (code "35") (name "Net-(J2-PadB5)") (class "Default")
      (node (ref "J2") (pin "B5") (pinfunction "B5_B5") (pintype "bidirectional"))
      (node (ref "R2-USB") (pin "1") (pinfunction "1_1") (pintype "passive"))
    )
    (net (code "36") (name "Net-(MCP73831-PROG)") (class "Default")
      (node (ref "MCP73831") (pin "5") (pinfunction "PROG_5") (pintype "input"))
      (node (ref "R2_BAT") (pin "2") (pinfunction "2_2") (pintype "passive"))
    )
    (net (code "37") (name "Net-(MCP73831-STAT)") (class "Default")
      (node (ref "MCP73831") (pin "1") (pinfunction "STAT_1") (pintype "output"))
      (node (ref "R1_BAT") (pin "1") (pinfunction "1_1") (pintype "passive"))
    )
    (net (code "38") (name "PREVGH") (class "Default")
      (node (ref "D5") (pin "1") (pinfunction "K_1") (pintype "bidirectional"))
      (node (ref "EPD_C9") (pin "1") (pinfunction "1_1") (pintype "passive"))
      (node (ref "J1") (pin "21") (pinfunction "21_21") (pintype "bidirectional"))
    )
    (net (code "39") (name "PREVGL") (class "Default")
      (node (ref "D4") (pin "2") (pinfunction "A_2") (pintype "bidirectional"))
      (node (ref "EPD_C11") (pin "1") (pinfunction "1_1") (pintype "passive"))
      (node (ref "J1") (pin "23") (pinfunction "23_23") (pintype "bidirectional"))
    )
    (net (code "40") (name "RESE") (class "Default")
      (node (ref "J1") (pin "3") (pinfunction "3_3") (pintype "bidirectional"))
      (node (ref "Q3") (pin "2") (pinfunction "S_2") (pintype "bidirectional"))
      (node (ref "R3") (pin "1") (pinfunction "1_1") (pintype "passive"))
    )
    (net (code "41") (name "RESE'") (class "Default")
      (node (ref "R2") (pin "2") (pinfunction "2_2") (pintype "passive"))
      (node (ref "R3") (pin "2") (pinfunction "2_2") (pintype "passive"))
      (node (ref "SJ1") (pin "2") (pinfunction "2_2") (pintype "passive"))
    )
    (net (code "42") (name "RESET") (class "Default")
      (node (ref "C5") (pin "1") (pinfunction "1_1") (pintype "passive"))
      (node (ref "IC1") (pin "1") (pinfunction "VOUT_1") (pintype "bidirectional"))
      (node (ref "RESET_BUTTON") (pin "3") (pinfunction "3_3") (pintype "passive"))
      (node (ref "RESET_BUTTON") (pin "4") (pinfunction "4_4") (pintype "passive"))
      (node (ref "R_RESET") (pin "2") (pinfunction "2_2") (pintype "passive"))
      (node (ref "U2") (pin "3") (pinfunction "EN_3") (pintype "input"))
    )
    (net (code "43") (name "RTC_RST") (class "Default")
      (node (ref "U2") (pin "16") (pinfunction "IO18_16") (pintype "bidirectional"))
      (node (ref "U3") (pin "4") (pinfunction "~{RST}_4") (pintype "input"))
    )
    (net (code "44") (name "RX") (class "Default")
      (node (ref "TP2") (pin "TP") (pinfunction "TP_TP") (pintype "input"))
      (node (ref "U2") (pin "24") (pinfunction "RXD0/GPIO17_24") (pintype "bidirectional"))
    )
    (net (code "45") (name "SCK") (class "Default")
      (node (ref "D10") (pin "1") (pinfunction "1_1") (pintype "passive"))
      (node (ref "J1") (pin "13") (pinfunction "13_13") (pintype "bidirectional"))
      (node (ref "J4") (pin "P5") (pinfunction "CLK_P5") (pintype "bidirectional"))
      (node (ref "R6") (pin "1") (pinfunction "1_1") (pintype "passive"))
      (node (ref "TP8") (pin "TP") (pinfunction "TP_TP") (pintype "input"))
      (node (ref "U1") (pin "6") (pinfunction "CLK_6") (pintype "input"))
      (node (ref "U2") (pin "6") (pinfunction "IO6_6") (pintype "bidirectional"))
    )
    (net (code "46") (name "SCL") (class "Default")
      (node (ref "J3") (pin "4") (pinfunction "4_4") (pintype "passive"))
      (node (ref "R2-PINH") (pin "1") (pinfunction "1_1") (pintype "passive"))
      (node (ref "SENSOR2") (pin "4") (pinfunction "SCK_4") (pintype "input"))
      (node (ref "U2") (pin "20") (pinfunction "IO22_20") (pintype "bidirectional"))
      (node (ref "U3") (pin "16") (pinfunction "SCL_16") (pintype "input"))
      (node (ref "U4") (pin "7") (pinfunction "SCL_7") (pintype "input"))
    )
    (net (code "47") (name "SDA") (class "Default")
      (node (ref "J3") (pin "3") (pinfunction "3_3") (pintype "passive"))
      (node (ref "R1_PINH") (pin "1") (pinfunction "1_1") (pintype "passive"))
      (node (ref "SENSOR2") (pin "3") (pinfunction "SDI_3") (pintype "bidirectional"))
      (node (ref "U2") (pin "19") (pinfunction "IO21_19") (pintype "bidirectional"))
      (node (ref "U3") (pin "15") (pinfunction "SDA_15") (pintype "bidirectional"))
      (node (ref "U4") (pin "8") (pinfunction "SDA_8") (pintype "bidirectional"))
    )
    (net (code "48") (name "SRC") (class "Default")
      (node (ref "C4") (pin "2") (pinfunction "2_2") (pintype "passive"))
      (node (ref "D5") (pin "2") (pinfunction "A_2") (pintype "bidirectional"))
      (node (ref "L1") (pin "1") (pinfunction "1_1") (pintype "passive"))
      (node (ref "Q3") (pin "3") (pinfunction "D_3") (pintype "bidirectional"))
    )
    (net (code "49") (name "SS_SD") (class "Default")
      (node (ref "D8") (pin "1") (pinfunction "1_1") (pintype "passive"))
      (node (ref "J4") (pin "P2") (pinfunction "CD/DAT3_P2") (pintype "bidirectional"))
      (node (ref "R10") (pin "1") (pinfunction "1_1") (pintype "passive"))
      (node (ref "U2") (pin "4") (pinfunction "IO4_4") (pintype "bidirectional"))
    )
    (net (code "50") (name "TX") (class "Default")
      (node (ref "TP1") (pin "TP") (pinfunction "TP_TP") (pintype "input"))
      (node (ref "U2") (pin "25") (pinfunction "TXD0/GPIO16_25") (pintype "bidirectional"))
    )
    (net (code "51") (name "USB_D+") (class "Default")
      (node (ref "D1") (pin "1") (pinfunction "I/O1_1_1") (pintype "bidirectional"))
      (node (ref "U2") (pin "14") (pinfunction "IO13_14") (pintype "bidirectional"))
    )
    (net (code "52") (name "USB_D-") (class "Default")
      (node (ref "D1") (pin "3") (pinfunction "I/O2_1_3") (pintype "bidirectional"))
      (node (ref "U2") (pin "13") (pinfunction "IO12_13") (pintype "bidirectional"))
    )
    (net (code "53") (name "VBAT") (class "Default")
      (node (ref "C2_BAT") (pin "1") (pinfunction "1_1") (pintype "passive"))
      (node (ref "MCP73831") (pin "3") (pinfunction "VBAT_3") (pintype "power_in"))
      (node (ref "Q1") (pin "3") (pinfunction "D_3") (pintype "bidirectional"))
      (node (ref "TP3") (pin "TP") (pinfunction "TP_TP") (pintype "input"))
      (node (ref "U4") (pin "2") (pinfunction "CELL_2") (pintype "power_in"))
      (node (ref "U4") (pin "3") (pinfunction "VDD_3") (pintype "power_in"))
    )
    (net (code "54") (name "VBUS") (class "Default")
      (node (ref "C1_BAT") (pin "1") (pinfunction "1_1") (pintype "passive"))
      (node (ref "C4_USB") (pin "1") (pinfunction "1_1") (pintype "passive"))
      (node (ref "C5_USB") (pin "1") (pinfunction "1_1") (pintype "passive"))
      (node (ref "CHG_LED") (pin "A") (pinfunction "A_A") (pintype "passive"))
      (node (ref "D1") (pin "5") (pinfunction "VBUS_5") (pintype "bidirectional"))
      (node (ref "D2") (pin "2") (pinfunction "ANODE_2") (pintype "bidirectional"))
      (node (ref "MCP73831") (pin "4") (pinfunction "VIN_4") (pintype "power_in"))
      (node (ref "PFMF.050.1") (pin "2") (pinfunction "2_2") (pintype "passive"))
      (node (ref "Q1") (pin "1") (pinfunction "G_1") (pintype "bidirectional"))
      (node (ref "R1_PWRUSB") (pin "2") (pinfunction "2_2") (pintype "passive"))
      (node (ref "TP14") (pin "TP") (pinfunction "TP_TP") (pintype "input"))
    )
    (net (code "55") (name "VRTC") (class "Default")
      (node (ref "C10_SUPERCAP") (pin "2") (pinfunction "2_2") (pintype "passive"))
      (node (ref "C8") (pin "1") (pinfunction "1_1") (pintype "passive"))
      (node (ref "R_CAPACITOR") (pin "1") (pinfunction "1_1") (pintype "passive"))
      (node (ref "U3") (pin "14") (pinfunction "VBAT_14") (pintype "power_in"))
    )
    (net (code "56") (name "VUSB") (class "Default")
      (node (ref "J2") (pin "A4") (pinfunction "A4_A4") (pintype "bidirectional"))
      (node (ref "J2") (pin "A9") (pinfunction "A9_A9") (pintype "bidirectional"))
      (node (ref "J2") (pin "B4") (pinfunction "B4_B4") (pintype "bidirectional"))
      (node (ref "J2") (pin "B9") (pinfunction "B9_B9") (pintype "bidirectional"))
      (node (ref "PFMF.050.1") (pin "1") (pinfunction "1_1") (pintype "passive"))
    )
    (net (code "57") (name "unconnected-(IC1-NC-Pad4)") (class "Default")
      (node (ref "IC1") (pin "4") (pinfunction "NC_4") (pintype "no_connect"))
    )
    (net (code "58") (name "unconnected-(IC4-NC-Pad4)") (class "Default")
      (node (ref "IC4") (pin "4") (pinfunction "NC_4") (pintype "no_connect"))
    )
    (net (code "59") (name "unconnected-(J1-Pad1)") (class "Default")
      (node (ref "J1") (pin "1") (pinfunction "1_1") (pintype "bidirectional"))
    )
    (net (code "60") (name "unconnected-(J1-Pad6)") (class "Default")
      (node (ref "J1") (pin "6") (pinfunction "6_6") (pintype "bidirectional"))
    )
    (net (code "61") (name "unconnected-(J1-Pad7)") (class "Default")
      (node (ref "J1") (pin "7") (pinfunction "7_7") (pintype "bidirectional"))
    )
    (net (code "62") (name "unconnected-(J2-PadA8)") (class "Default")
      (node (ref "J2") (pin "A8") (pinfunction "A8_A8") (pintype "bidirectional"))
    )
    (net (code "63") (name "unconnected-(J2-PadB8)") (class "Default")
      (node (ref "J2") (pin "B8") (pinfunction "B8_B8") (pintype "bidirectional"))
    )
    (net (code "64") (name "unconnected-(J4-DAT1-PadP8)") (class "Default")
      (node (ref "J4") (pin "P8") (pinfunction "DAT1_P8") (pintype "bidirectional"))
    )
    (net (code "65") (name "unconnected-(J4-DAT2-PadP1)") (class "Default")
      (node (ref "J4") (pin "P1") (pinfunction "DAT2_P1") (pintype "bidirectional"))
    )
    (net (code "66") (name "unconnected-(J4-DETECTION_1-PadS1)") (class "Default")
      (node (ref "J4") (pin "S1") (pinfunction "DETECTION_1_S1") (pintype "bidirectional"))
    )
    (net (code "67") (name "unconnected-(J4-DETECTION_2-PadS2)") (class "Default")
      (node (ref "J4") (pin "S2") (pinfunction "DETECTION_2_S2") (pintype "bidirectional"))
    )
    (net (code "68") (name "unconnected-(U2-NC-Pad22)") (class "Default")
      (node (ref "U2") (pin "22") (pinfunction "NC_22") (pintype "no_connect"))
    )
    (net (code "69") (name "unconnected-(U4-~{ALERT}-Pad5)") (class "Default")
      (node (ref "U4") (pin "5") (pinfunction "~{ALERT}_5") (pintype "output"))
    )
  )
)
